# scheme_easy_eda.net
KiCad netlist of a schematic drawn in EasyEDA
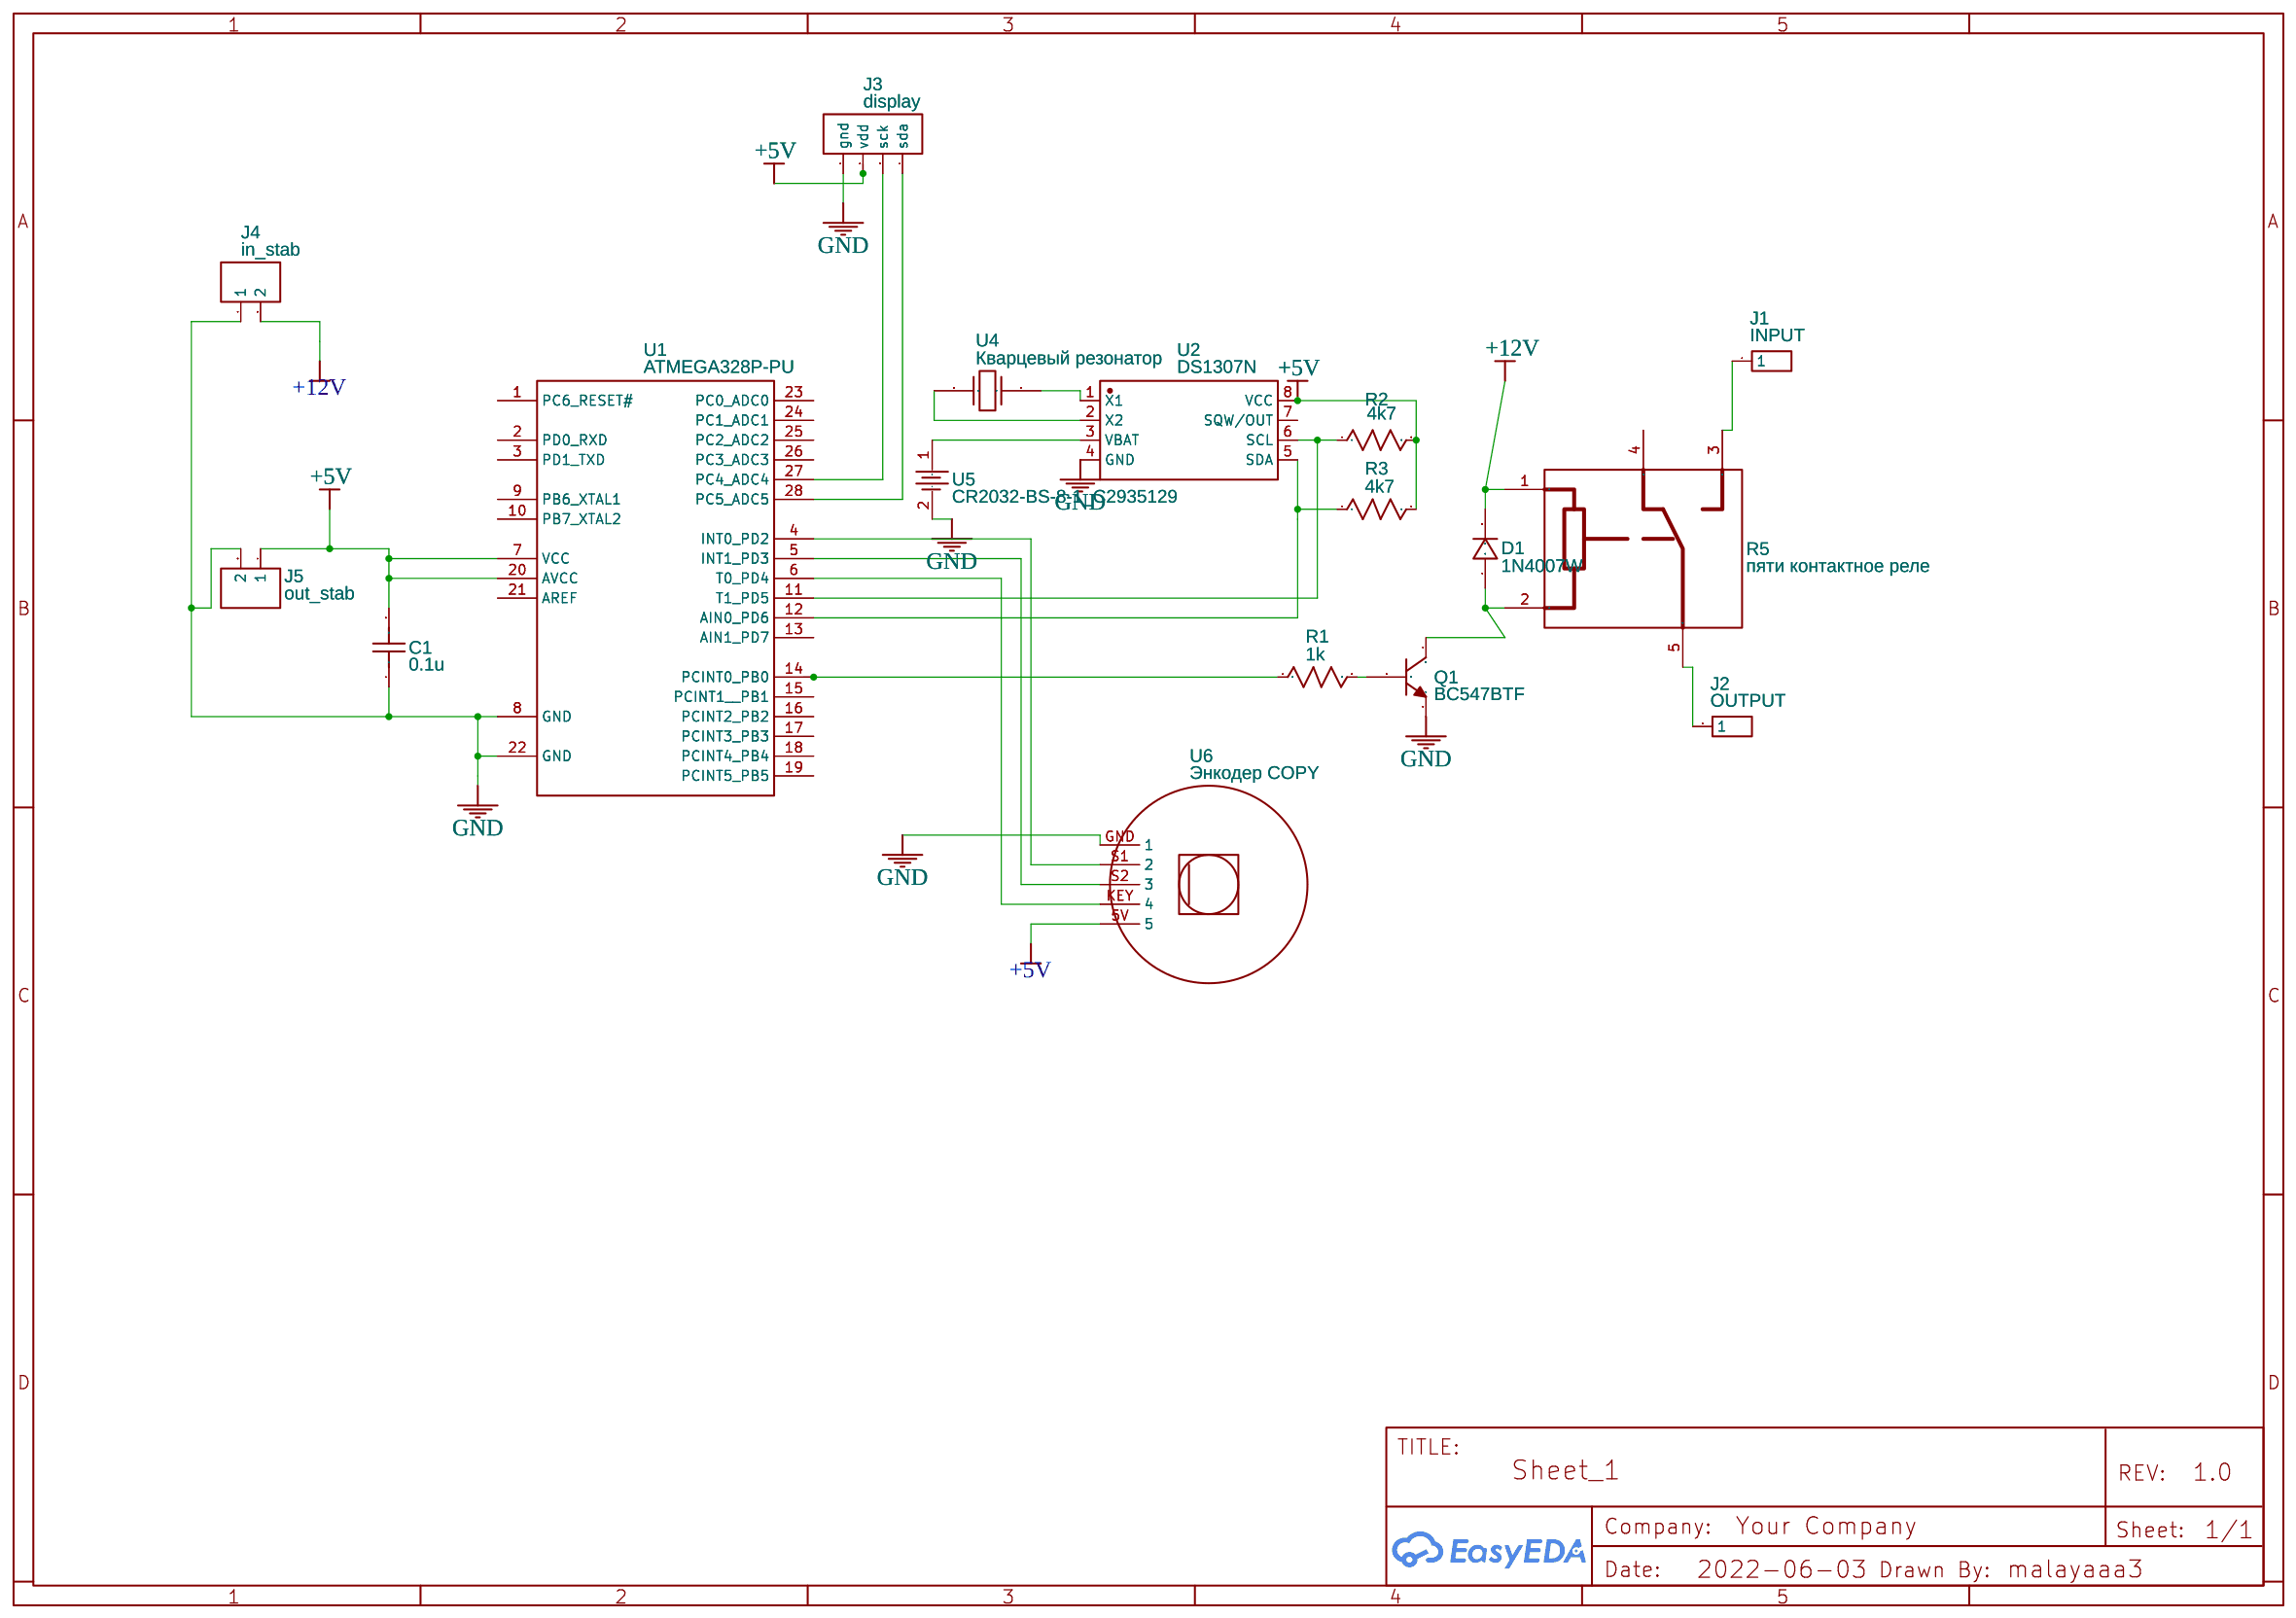
[diagram p0: schematic sheet]

(export (version "E")
  (design (tool "Eeschema 10.0.6"))
  (components
    (comp (ref "C1") (value "0.1u") (libsource (lib "") (part "C_0603_US")))
    (comp (ref "D1")
      (value "1N4007W")
      (fields (field (name "BOM_Supplier Part") "C328592"))
      (libsource (lib "") (part "1N4007W"))
    )
    (comp (ref "J1")
      (value "INPUT")
      (fields (field (name "BOM_Supplier Part") "C81276"))
      (libsource (lib "") (part "HDR-M-2.54_1x1"))
    )
    (comp (ref "J2")
      (value "OUTPUT")
      (fields (field (name "BOM_Supplier Part") "C81276"))
      (libsource (lib "") (part "HDR-M-2.54_1x1"))
    )
    (comp (ref "J3")
      (value "display")
      (fields (field (name "BOM_Supplier Part") "C124378"))
      (libsource (lib "") (part "HDR-M-2.54_1x4"))
    )
    (comp (ref "J4")
      (value "in_stab")
      (fields (field (name "BOM_Supplier Part") "C124375"))
      (libsource (lib "") (part "HDR-M-2.54_1x2_1"))
    )
    (comp (ref "J5")
      (value "out_stab")
      (fields (field (name "BOM_Supplier Part") "C124375"))
      (libsource (lib "") (part "HDR-M-2.54_1x2"))
    )
    (comp (ref "Q1")
      (value "BC547BTF")
      (fields (field (name "BOM_Supplier Part") "C900798"))
      (libsource (lib "") (part "BC547BTF"))
    )
    (comp (ref "R1") (value "1k") (libsource (lib "") (part "R_0603_US")))
    (comp (ref "R2") (value "4k7") (libsource (lib "") (part "R_0603_US")))
    (comp (ref "R3") (value "4k7") (libsource (lib "") (part "R_0603_US")))
    (comp (ref "R5") (value "пяти контактное реле") (libsource (lib "") (part "пяти контактное реле")))
    (comp (ref "U1")
      (value "ATMEGA328P-PU")
      (fields (field (name "BOM_Supplier Part") "C33901"))
      (libsource (lib "") (part "ATMEGA328P-PU"))
    )
    (comp (ref "U2")
      (value "DS1307N")
      (fields (field (name "BOM_Supplier Part") "C434596"))
      (libsource (lib "") (part "DS1307N"))
    )
    (comp (ref "U4") (value "Кварцевый резонатор") (libsource (lib "") (part "Кварцевый резонатор")))
    (comp (ref "U5")
      (value "CR2032-BS-8-1_C2935129")
      (fields
        (field (name "BOM_Manufacturer Part") "CR2032-BS-8-1")
        (field (name "BOM_Supplier Part") "C2935129")
      )
      (libsource (lib "") (part "CR2032-BS-8-1_C2935129"))
    )
    (comp (ref "U6")
      (value "Энкодер COPY")
      (fields (field (name "BOM_Manufacturer Part") "Энкодер"))
      (libsource (lib "") (part "Энкодер COPY"))
    )
  )
  (nets
    (net (code "1") (name "+5V") (class "Default")
      (node (ref "C1") (pin "2") (pinfunction "2_2") (pintype "unspecified"))
      (node (ref "J3") (pin "2") (pinfunction "vdd_2") (pintype "unspecified"))
      (node (ref "J5") (pin "1") (pinfunction "1_1") (pintype "unspecified"))
      (node (ref "R2") (pin "2") (pinfunction "2_2") (pintype "unspecified"))
      (node (ref "R3") (pin "2") (pinfunction "2_2") (pintype "unspecified"))
      (node (ref "U1") (pin "20") (pinfunction "AVCC_20") (pintype "passive"))
      (node (ref "U1") (pin "7") (pinfunction "VCC_7") (pintype "passive"))
      (node (ref "U2") (pin "8") (pinfunction "VCC_8") (pintype "unspecified"))
      (node (ref "U6") (pin "5V") (pinfunction "5_5V") (pintype "unspecified"))
    )
    (net (code "2") (name "+12V") (class "Default")
      (node (ref "D1") (pin "2") (pinfunction "1_2") (pintype "input"))
      (node (ref "J4") (pin "2") (pinfunction "2_2") (pintype "unspecified"))
      (node (ref "R5") (pin "1") (pinfunction "2_1") (pintype "unspecified"))
    )
    (net (code "3") (name "GND") (class "Default")
      (node (ref "C1") (pin "1") (pinfunction "1_1") (pintype "unspecified"))
      (node (ref "J3") (pin "1") (pinfunction "gnd_1") (pintype "unspecified"))
      (node (ref "J4") (pin "1") (pinfunction "1_1") (pintype "unspecified"))
      (node (ref "J5") (pin "2") (pinfunction "2_2") (pintype "unspecified"))
      (node (ref "Q1") (pin "3") (pinfunction "E_3") (pintype "unspecified"))
      (node (ref "U1") (pin "22") (pinfunction "GND_22") (pintype "passive"))
      (node (ref "U1") (pin "8") (pinfunction "GND_8") (pintype "passive"))
      (node (ref "U2") (pin "4") (pinfunction "GND_4") (pintype "unspecified"))
      (node (ref "U5") (pin "2") (pinfunction "-_2") (pintype "input"))
      (node (ref "U6") (pin "GND") (pinfunction "1_GND") (pintype "unspecified"))
    )
    (net (code "4") (name "Net-(D1-2)") (class "Default")
      (node (ref "D1") (pin "1") (pinfunction "2_1") (pintype "output"))
      (node (ref "Q1") (pin "1") (pinfunction "C_1") (pintype "unspecified"))
      (node (ref "R5") (pin "2") (pinfunction "1_2") (pintype "unspecified"))
    )
    (net (code "5") (name "Net-(J2-Pad1)") (class "Default")
      (node (ref "J2") (pin "1") (pinfunction "1_1") (pintype "input"))
      (node (ref "R5") (pin "5") (pinfunction "5_5") (pintype "unspecified"))
    )
    (net (code "6") (name "Net-(J3-sck)") (class "Default")
      (node (ref "J3") (pin "3") (pinfunction "sck_3") (pintype "unspecified"))
      (node (ref "U1") (pin "27") (pinfunction "PC4_ADC4_27") (pintype "bidirectional"))
    )
    (net (code "7") (name "Net-(J3-sda)") (class "Default")
      (node (ref "J3") (pin "4") (pinfunction "sda_4") (pintype "unspecified"))
      (node (ref "U1") (pin "28") (pinfunction "PC5_ADC5_28") (pintype "bidirectional"))
    )
    (net (code "8") (name "Net-(Q1-B)") (class "Default")
      (node (ref "Q1") (pin "2") (pinfunction "B_2") (pintype "unspecified"))
      (node (ref "R1") (pin "2") (pinfunction "2_2") (pintype "unspecified"))
    )
    (net (code "9") (name "Net-(R5-4)") (class "Default")
      (node (ref "J1") (pin "1") (pinfunction "1_1") (pintype "input"))
      (node (ref "R5") (pin "3") (pinfunction "4_3") (pintype "unspecified"))
    )
    (net (code "10") (name "Net-(U1-AIN0_PD6)") (class "Default")
      (node (ref "R3") (pin "1") (pinfunction "1_1") (pintype "unspecified"))
      (node (ref "U1") (pin "12") (pinfunction "AIN0_PD6_12") (pintype "bidirectional"))
      (node (ref "U2") (pin "5") (pinfunction "SDA_5") (pintype "unspecified"))
    )
    (net (code "11") (name "Net-(U1-INT0_PD2)") (class "Default")
      (node (ref "U1") (pin "4") (pinfunction "INT0_PD2_4") (pintype "bidirectional"))
      (node (ref "U6") (pin "S1") (pinfunction "2_S1") (pintype "unspecified"))
    )
    (net (code "12") (name "Net-(U1-INT1_PD3)") (class "Default")
      (node (ref "U1") (pin "5") (pinfunction "INT1_PD3_5") (pintype "bidirectional"))
      (node (ref "U6") (pin "S2") (pinfunction "3_S2") (pintype "unspecified"))
    )
    (net (code "13") (name "Net-(U1-PCINT0_PB0)") (class "Default")
      (node (ref "R1") (pin "1") (pinfunction "1_1") (pintype "unspecified"))
      (node (ref "U1") (pin "14") (pinfunction "PCINT0_PB0_14") (pintype "bidirectional"))
    )
    (net (code "14") (name "Net-(U1-T0_PD4)") (class "Default")
      (node (ref "U1") (pin "6") (pinfunction "T0_PD4_6") (pintype "bidirectional"))
      (node (ref "U6") (pin "KEY") (pinfunction "4_KEY") (pintype "unspecified"))
    )
    (net (code "15") (name "Net-(U1-T1_PD5)") (class "Default")
      (node (ref "R2") (pin "1") (pinfunction "1_1") (pintype "unspecified"))
      (node (ref "U1") (pin "11") (pinfunction "T1_PD5_11") (pintype "bidirectional"))
      (node (ref "U2") (pin "6") (pinfunction "SCL_6") (pintype "unspecified"))
    )
    (net (code "16") (name "Net-(U2-VBAT)") (class "Default")
      (node (ref "U2") (pin "3") (pinfunction "VBAT_3") (pintype "unspecified"))
      (node (ref "U5") (pin "1") (pinfunction "+_1") (pintype "input"))
    )
    (net (code "17") (name "Net-(U2-X1)") (class "Default")
      (node (ref "U2") (pin "1") (pinfunction "X1_1") (pintype "unspecified"))
      (node (ref "U4") (pin "1") (pinfunction "1_1") (pintype "unspecified"))
    )
    (net (code "18") (name "Net-(U2-X2)") (class "Default")
      (node (ref "U2") (pin "2") (pinfunction "X2_2") (pintype "unspecified"))
      (node (ref "U4") (pin "2") (pinfunction "2_2") (pintype "unspecified"))
    )
    (net (code "19") (name "unconnected-(R5-3-Pad4)") (class "Default")
      (node (ref "R5") (pin "4") (pinfunction "3_4") (pintype "unspecified"))
    )
    (net (code "20") (name "unconnected-(U1-AIN1_PD7-Pad13)") (class "Default")
      (node (ref "U1") (pin "13") (pinfunction "AIN1_PD7_13") (pintype "bidirectional"))
    )
    (net (code "21") (name "unconnected-(U1-AREF-Pad21)") (class "Default")
      (node (ref "U1") (pin "21") (pinfunction "AREF_21") (pintype "passive"))
    )
    (net (code "22") (name "unconnected-(U1-PB6_XTAL1-Pad9)") (class "Default")
      (node (ref "U1") (pin "9") (pinfunction "PB6_XTAL1_9") (pintype "bidirectional"))
    )
    (net (code "23") (name "unconnected-(U1-PB7_XTAL2-Pad10)") (class "Default")
      (node (ref "U1") (pin "10") (pinfunction "PB7_XTAL2_10") (pintype "bidirectional"))
    )
    (net (code "24") (name "unconnected-(U1-PC0_ADC0-Pad23)") (class "Default")
      (node (ref "U1") (pin "23") (pinfunction "PC0_ADC0_23") (pintype "bidirectional"))
    )
    (net (code "25") (name "unconnected-(U1-PC1_ADC1-Pad24)") (class "Default")
      (node (ref "U1") (pin "24") (pinfunction "PC1_ADC1_24") (pintype "bidirectional"))
    )
    (net (code "26") (name "unconnected-(U1-PC2_ADC2-Pad25)") (class "Default")
      (node (ref "U1") (pin "25") (pinfunction "PC2_ADC2_25") (pintype "bidirectional"))
    )
    (net (code "27") (name "unconnected-(U1-PC3_ADC3-Pad26)") (class "Default")
      (node (ref "U1") (pin "26") (pinfunction "PC3_ADC3_26") (pintype "bidirectional"))
    )
    (net (code "28") (name "unconnected-(U1-PC6_RESET#-Pad1)") (class "Default")
      (node (ref "U1") (pin "1") (pinfunction "PC6_RESET#_1") (pintype "bidirectional"))
    )
    (net (code "29") (name "unconnected-(U1-PCINT1__PB1-Pad15)") (class "Default")
      (node (ref "U1") (pin "15") (pinfunction "PCINT1__PB1_15") (pintype "bidirectional"))
    )
    (net (code "30") (name "unconnected-(U1-PCINT2_PB2-Pad16)") (class "Default")
      (node (ref "U1") (pin "16") (pinfunction "PCINT2_PB2_16") (pintype "bidirectional"))
    )
    (net (code "31") (name "unconnected-(U1-PCINT3_PB3-Pad17)") (class "Default")
      (node (ref "U1") (pin "17") (pinfunction "PCINT3_PB3_17") (pintype "bidirectional"))
    )
    (net (code "32") (name "unconnected-(U1-PCINT4_PB4-Pad18)") (class "Default")
      (node (ref "U1") (pin "18") (pinfunction "PCINT4_PB4_18") (pintype "bidirectional"))
    )
    (net (code "33") (name "unconnected-(U1-PCINT5_PB5-Pad19)") (class "Default")
      (node (ref "U1") (pin "19") (pinfunction "PCINT5_PB5_19") (pintype "bidirectional"))
    )
    (net (code "34") (name "unconnected-(U1-PD0_RXD-Pad2)") (class "Default")
      (node (ref "U1") (pin "2") (pinfunction "PD0_RXD_2") (pintype "bidirectional"))
    )
    (net (code "35") (name "unconnected-(U1-PD1_TXD-Pad3)") (class "Default")
      (node (ref "U1") (pin "3") (pinfunction "PD1_TXD_3") (pintype "bidirectional"))
    )
    (net (code "36") (name "unconnected-(U2-SQW{slash}OUT-Pad7)") (class "Default")
      (node (ref "U2") (pin "7") (pinfunction "SQW/OUT_7") (pintype "unspecified"))
    )
  )
)
